# EEPROM_Modul.net
KiCad netlist of a schematic drawn in EAGLE
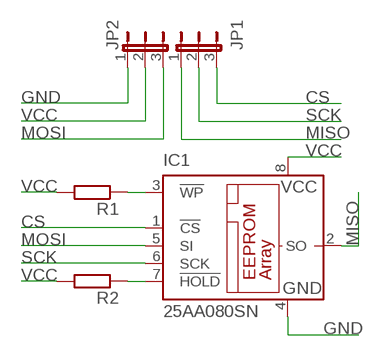
[diagram p0: schematic, sheet 1]

(export (version "E")
  (design (tool "Eeschema 10.0.6"))
  (components
    (comp (ref "IC1")
      (value "25AA080SN")
      (footprint "eagle-import:SO-08")
      (fields (field (name "MF") "MICROCHIP") (field (name "MPN") "25AA080/SN"))
      (libsource (lib "eagle-import") (part "25SNAA080"))
    )
    (comp (ref "JP1")
      (value "JP2E")
      (footprint "eagle-import:JP2")
      (libsource (lib "eagle-import") (part "JP2E"))
    )
    (comp (ref "JP2")
      (value "JP2E")
      (footprint "eagle-import:JP2")
      (libsource (lib "eagle-import") (part "JP2E"))
    )
    (comp (ref "R1")
      (value "R-EU_R0805")
      (footprint "eagle-import:R0805")
      (libsource (lib "eagle-import") (part "R-EU_R0805"))
    )
    (comp (ref "R2")
      (value "R-EU_R0805")
      (footprint "eagle-import:R0805")
      (libsource (lib "eagle-import") (part "R-EU_R0805"))
    )
  )
  (nets
    (net (code "1") (name "/CS") (class "Default")
      (node (ref "IC1") (pin "1") (pinfunction "~{CS}_1") (pintype "input"))
      (node (ref "JP1") (pin "3") (pinfunction "3_3") (pintype "passive"))
    )
    (net (code "2") (name "/GND") (class "Default")
      (node (ref "IC1") (pin "4") (pinfunction "GND_4") (pintype "power_in"))
      (node (ref "JP2") (pin "1") (pinfunction "1_1") (pintype "passive"))
    )
    (net (code "3") (name "/MISO") (class "Default")
      (node (ref "IC1") (pin "2") (pinfunction "SO_2") (pintype "bidirectional"))
      (node (ref "JP1") (pin "1") (pinfunction "1_1") (pintype "passive"))
    )
    (net (code "4") (name "/MOSI") (class "Default")
      (node (ref "IC1") (pin "5") (pinfunction "SI_5") (pintype "input"))
      (node (ref "JP2") (pin "3") (pinfunction "3_3") (pintype "passive"))
    )
    (net (code "5") (name "/SCK") (class "Default")
      (node (ref "IC1") (pin "6") (pinfunction "SCK_6") (pintype "input"))
      (node (ref "JP1") (pin "2") (pinfunction "2_2") (pintype "passive"))
    )
    (net (code "6") (name "/VCC") (class "Default")
      (node (ref "IC1") (pin "8") (pinfunction "VCC_8") (pintype "power_in"))
      (node (ref "JP2") (pin "2") (pinfunction "2_2") (pintype "passive"))
      (node (ref "R1") (pin "2") (pinfunction "2_2") (pintype "passive"))
      (node (ref "R2") (pin "2") (pinfunction "2_2") (pintype "passive"))
    )
    (net (code "7") (name "Net-(IC1-~{HOLD})") (class "Default")
      (node (ref "IC1") (pin "7") (pinfunction "~{HOLD}_7") (pintype "input"))
      (node (ref "R2") (pin "1") (pinfunction "1_1") (pintype "passive"))
    )
    (net (code "8") (name "Net-(IC1-~{WP})") (class "Default")
      (node (ref "IC1") (pin "3") (pinfunction "~{WP}_3") (pintype "input"))
      (node (ref "R1") (pin "1") (pinfunction "1_1") (pintype "passive"))
    )
  )
)
